# sch.net
KiCad netlist of a schematic drawn in Altium Designer
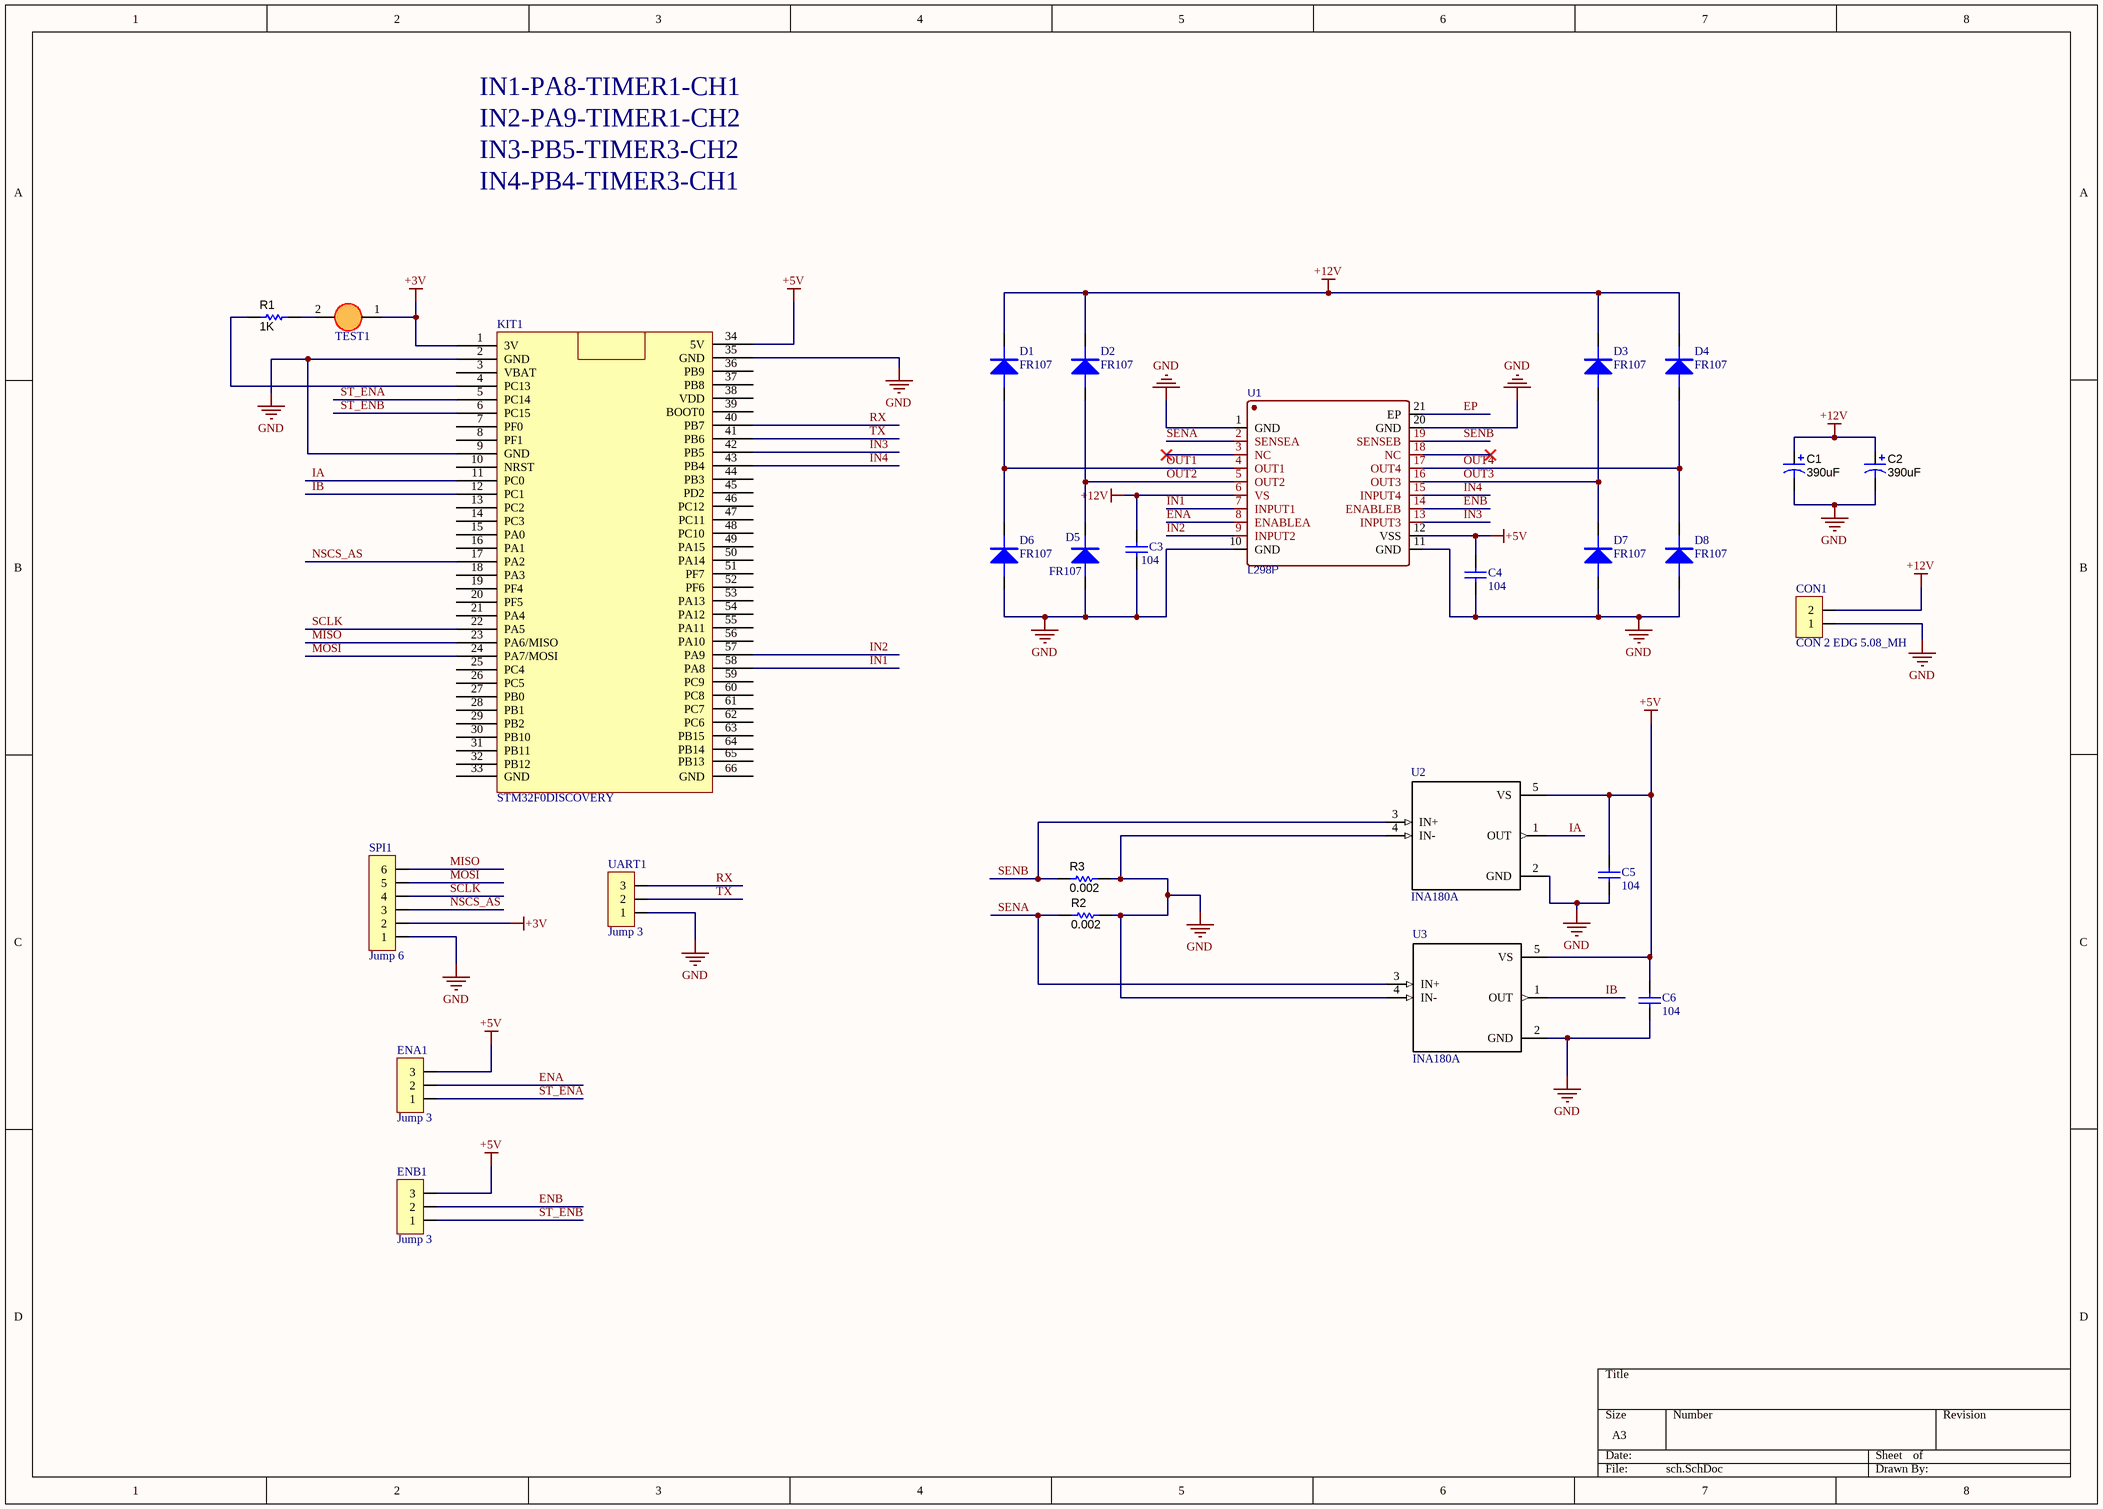
[diagram p0: sch.SchDoc]

(export (version "E")
  (design (tool "Eeschema 10.0.6"))
  (components
    (comp (ref "C1")
      (value "390uF")
      (footprint "CAP_12.5 X 25")
      (description "CAP ALUM 390UF 20% 50V RADIAL")
      (fields
        (field (name "PARTNUMBER") "UHW1H391MPD6")
        (field (name "MANUFACTURER") "Nichicon")
        (field (name "VALUEDISPLAYED") "390uF")
        (field (name "PUBLISHER") "Texas Instruments")
      )
      (libsource (lib "mySch") (part "Capacitor TuHoa"))
    )
    (comp (ref "C2")
      (value "390uF")
      (footprint "CAP_12.5 X 25")
      (description "CAP ALUM 390UF 20% 50V RADIAL")
      (fields
        (field (name "PARTNUMBER") "UHW1H391MPD6")
        (field (name "MANUFACTURER") "Nichicon")
        (field (name "VALUEDISPLAYED") "390uF")
        (field (name "PUBLISHER") "Texas Instruments")
      )
      (libsource (lib "mySch") (part "Capacitor TuHoa"))
    )
    (comp (ref "C3")
      (value "104")
      (footprint "TU_SMD_0805")
      (description "Ceramic Chip Capacitor - Standard")
      (fields (field (name "PUBLISHER") "Altium Limited"))
      (libsource (lib "mySch") (part "Capacitor 0805"))
    )
    (comp (ref "C4")
      (value "104")
      (footprint "TU_SMD_0805")
      (description "Ceramic Chip Capacitor - Standard")
      (fields (field (name "PUBLISHER") "Altium Limited"))
      (libsource (lib "mySch") (part "Capacitor 0805"))
    )
    (comp (ref "C5")
      (value "104")
      (footprint "TU_SMD_0805")
      (description "Ceramic Chip Capacitor - Standard")
      (fields (field (name "PUBLISHER") "Altium Limited"))
      (libsource (lib "mySch") (part "Capacitor 0805"))
    )
    (comp (ref "C6")
      (value "104")
      (footprint "TU_SMD_0805")
      (description "Ceramic Chip Capacitor - Standard")
      (fields (field (name "PUBLISHER") "Altium Limited"))
      (libsource (lib "mySch") (part "Capacitor 0805"))
    )
    (comp (ref "CON1")
      (value "CON 2 EDG 5.08_MH")
      (footprint "CON 2 EDG 5.08")
      (description "CON 2 EDG 5.08 (xanh cong)")
      (libsource (lib "mySch") (part "CON 2 EDG 5.08_MH"))
    )
    (comp (ref "D1")
      (value "FR107")
      (footprint "D2A")
      (description "Diode 1N4148 DO35 450mA 100V ( 1N4148 DIP)")
      (libsource (lib "mySch") (part "Diode 1N4148 DO35 450mA 100V ( 1N4148 DIP)_MH"))
    )
    (comp (ref "D2")
      (value "FR107")
      (footprint "D2A")
      (description "Diode 1N4148 DO35 450mA 100V ( 1N4148 DIP)")
      (libsource (lib "mySch") (part "Diode 1N4148 DO35 450mA 100V ( 1N4148 DIP)_MH"))
    )
    (comp (ref "D3")
      (value "FR107")
      (footprint "D2A")
      (description "Diode 1N4148 DO35 450mA 100V ( 1N4148 DIP)")
      (libsource (lib "mySch") (part "Diode 1N4148 DO35 450mA 100V ( 1N4148 DIP)_MH"))
    )
    (comp (ref "D4")
      (value "FR107")
      (footprint "D2A")
      (description "Diode 1N4148 DO35 450mA 100V ( 1N4148 DIP)")
      (libsource (lib "mySch") (part "Diode 1N4148 DO35 450mA 100V ( 1N4148 DIP)_MH"))
    )
    (comp (ref "D5")
      (value "FR107")
      (footprint "D2A")
      (description "Diode 1N4148 DO35 450mA 100V ( 1N4148 DIP)")
      (libsource (lib "mySch") (part "Diode 1N4148 DO35 450mA 100V ( 1N4148 DIP)_MH"))
    )
    (comp (ref "D6")
      (value "FR107")
      (footprint "D2A")
      (description "Diode 1N4148 DO35 450mA 100V ( 1N4148 DIP)")
      (libsource (lib "mySch") (part "Diode 1N4148 DO35 450mA 100V ( 1N4148 DIP)_MH"))
    )
    (comp (ref "D7")
      (value "FR107")
      (footprint "D2A")
      (description "Diode 1N4148 DO35 450mA 100V ( 1N4148 DIP)")
      (libsource (lib "mySch") (part "Diode 1N4148 DO35 450mA 100V ( 1N4148 DIP)_MH"))
    )
    (comp (ref "D8")
      (value "FR107")
      (footprint "D2A")
      (description "Diode 1N4148 DO35 450mA 100V ( 1N4148 DIP)")
      (libsource (lib "mySch") (part "Diode 1N4148 DO35 450mA 100V ( 1N4148 DIP)_MH"))
    )
    (comp (ref "ENA1")
      (value "Jump 3")
      (footprint "Jump 3")
      (description "Jump 3P 2.54")
      (libsource (lib "mySch") (part "Jump 3"))
    )
    (comp (ref "ENB1")
      (value "Jump 3")
      (footprint "Jump 3")
      (description "Jump 3P 2.54")
      (libsource (lib "mySch") (part "Jump 3"))
    )
    (comp (ref "KIT1")
      (value "STM32F0DISCOVERY")
      (footprint "STM32F0DISCOVERY")
      (libsource (lib "mySch") (part "STM32F0DISCOVERY"))
    )
    (comp (ref "R1")
      (value "1K")
      (footprint "Tro SMD 0805")
      (description "RES, 100, 1%, 0.1 W, 0402")
      (fields
        (field (name "PARTNUMBER") "ERJ-2RKF1000X")
        (field (name "MANUFACTURER") "Panasonic")
        (field (name "PUBLISHER") "Texas Instruments")
      )
      (libsource (lib "mySch") (part "R nho"))
    )
    (comp (ref "R2")
      (value "0.002")
      (footprint "2512_R")
      (description "RES, 100, 1%, 0.1 W, 0402")
      (fields
        (field (name "PARTNUMBER") "ERJ-2RKF1000X")
        (field (name "MANUFACTURER") "Panasonic")
        (field (name "PUBLISHER") "Texas Instruments")
      )
      (libsource (lib "mySch") (part "R nho"))
    )
    (comp (ref "R3")
      (value "0.002")
      (footprint "2512_R")
      (description "RES, 100, 1%, 0.1 W, 0402")
      (fields
        (field (name "PARTNUMBER") "ERJ-2RKF1000X")
        (field (name "MANUFACTURER") "Panasonic")
        (field (name "PUBLISHER") "Texas Instruments")
      )
      (libsource (lib "mySch") (part "R nho"))
    )
    (comp (ref "SPI1")
      (value "Jump 6")
      (footprint "Jump 6")
      (description "Jump 6P 2.54")
      (libsource (lib "mySch") (part "Jump 6"))
    )
    (comp (ref "TEST1")
      (value "LED")
      (footprint "LED_0805")
      (description "LED 3mm")
      (libsource (lib "mySch") (part "LED SMD_0805_MH"))
    )
    (comp (ref "U1")
      (value "L298P")
      (footprint "SOIC127P1420X360-21N")
      (fields (field (name "BOM_SUPPLIER PART") "C85595"))
      (libsource (lib "mySch") (part "L298P"))
    )
    (comp (ref "U2")
      (value "INA180A")
      (footprint "SOT95P280X145-5N")
      (libsource (lib "mySch") (part "INA180A"))
    )
    (comp (ref "U3")
      (value "INA180A")
      (footprint "SOT95P280X145-5N")
      (libsource (lib "mySch") (part "INA180A"))
    )
    (comp (ref "UART1")
      (value "Jump 3")
      (footprint "Jump 3")
      (description "Jump 3P 2.54")
      (libsource (lib "mySch") (part "Jump 3"))
    )
  )
  (nets
    (net (code "1") (name "+3V") (class "Default")
      (node (ref "KIT1") (pin "1") (pinfunction "3V_1") (pintype "passive"))
      (node (ref "SPI1") (pin "2") (pinfunction "2_2") (pintype "passive"))
      (node (ref "TEST1") (pin "1") (pinfunction "A_1") (pintype "passive"))
    )
    (net (code "2") (name "+5V") (class "Default")
      (node (ref "C4") (pin "2") (pinfunction "2_2") (pintype "passive"))
      (node (ref "C5") (pin "2") (pinfunction "2_2") (pintype "passive"))
      (node (ref "C6") (pin "2") (pinfunction "2_2") (pintype "passive"))
      (node (ref "ENA1") (pin "3") (pinfunction "3_3") (pintype "passive"))
      (node (ref "ENB1") (pin "3") (pinfunction "3_3") (pintype "passive"))
      (node (ref "KIT1") (pin "34") (pinfunction "5V_34") (pintype "passive"))
      (node (ref "U1") (pin "12") (pinfunction "VSS_12") (pintype "passive"))
      (node (ref "U2") (pin "5") (pinfunction "VS_5") (pintype "power_in"))
      (node (ref "U3") (pin "5") (pinfunction "VS_5") (pintype "power_in"))
    )
    (net (code "3") (name "+12V") (class "Default")
      (node (ref "C1") (pin "1") (pinfunction "+_1") (pintype "passive"))
      (node (ref "C2") (pin "1") (pinfunction "+_1") (pintype "passive"))
      (node (ref "C3") (pin "2") (pinfunction "2_2") (pintype "passive"))
      (node (ref "CON1") (pin "2") (pinfunction "2_2") (pintype "passive"))
      (node (ref "D1") (pin "2") (pinfunction "2_2") (pintype "passive"))
      (node (ref "D2") (pin "2") (pinfunction "2_2") (pintype "passive"))
      (node (ref "D3") (pin "2") (pinfunction "2_2") (pintype "passive"))
      (node (ref "D4") (pin "2") (pinfunction "2_2") (pintype "passive"))
      (node (ref "U1") (pin "6") (pinfunction "VS_6") (pintype "passive"))
    )
    (net (code "4") (name "/ENA") (class "Default")
      (node (ref "ENA1") (pin "2") (pinfunction "2_2") (pintype "passive"))
      (node (ref "U1") (pin "8") (pinfunction "ENABLEA_8") (pintype "passive"))
    )
    (net (code "5") (name "/ENB") (class "Default")
      (node (ref "ENB1") (pin "2") (pinfunction "2_2") (pintype "passive"))
      (node (ref "U1") (pin "14") (pinfunction "ENABLEB_14") (pintype "passive"))
    )
    (net (code "6") (name "/EP") (class "Default")
      (node (ref "U1") (pin "21") (pinfunction "EP_21") (pintype "passive"))
    )
    (net (code "7") (name "/IA") (class "Default")
      (node (ref "KIT1") (pin "11") (pinfunction "PC0_11") (pintype "passive"))
      (node (ref "U2") (pin "1") (pinfunction "OUT_1") (pintype "output"))
    )
    (net (code "8") (name "/IB") (class "Default")
      (node (ref "KIT1") (pin "12") (pinfunction "PC1_12") (pintype "passive"))
      (node (ref "U3") (pin "1") (pinfunction "OUT_1") (pintype "output"))
    )
    (net (code "9") (name "/IN1") (class "Default")
      (node (ref "KIT1") (pin "58") (pinfunction "PA8_58") (pintype "passive"))
      (node (ref "U1") (pin "7") (pinfunction "INPUT1_7") (pintype "passive"))
    )
    (net (code "10") (name "/IN2") (class "Default")
      (node (ref "KIT1") (pin "57") (pinfunction "PA9_57") (pintype "passive"))
      (node (ref "U1") (pin "9") (pinfunction "INPUT2_9") (pintype "passive"))
    )
    (net (code "11") (name "/IN3") (class "Default")
      (node (ref "KIT1") (pin "42") (pinfunction "PB5_42") (pintype "passive"))
      (node (ref "U1") (pin "13") (pinfunction "INPUT3_13") (pintype "passive"))
    )
    (net (code "12") (name "/IN4") (class "Default")
      (node (ref "KIT1") (pin "43") (pinfunction "PB4_43") (pintype "passive"))
      (node (ref "U1") (pin "15") (pinfunction "INPUT4_15") (pintype "passive"))
    )
    (net (code "13") (name "/MISO") (class "Default")
      (node (ref "KIT1") (pin "23") (pinfunction "PA6/MISO_23") (pintype "passive"))
      (node (ref "SPI1") (pin "6") (pinfunction "6_6") (pintype "passive"))
    )
    (net (code "14") (name "/MOSI") (class "Default")
      (node (ref "KIT1") (pin "24") (pinfunction "PA7/MOSI_24") (pintype "passive"))
      (node (ref "SPI1") (pin "5") (pinfunction "5_5") (pintype "passive"))
    )
    (net (code "15") (name "/NSCS_AS") (class "Default")
      (node (ref "KIT1") (pin "17") (pinfunction "PA2_17") (pintype "passive"))
      (node (ref "SPI1") (pin "3") (pinfunction "3_3") (pintype "passive"))
    )
    (net (code "16") (name "/OUT1") (class "Default")
      (node (ref "D1") (pin "1") (pinfunction "1_1") (pintype "passive"))
      (node (ref "D6") (pin "2") (pinfunction "2_2") (pintype "passive"))
      (node (ref "U1") (pin "4") (pinfunction "OUT1_4") (pintype "passive"))
    )
    (net (code "17") (name "/OUT2") (class "Default")
      (node (ref "D2") (pin "1") (pinfunction "1_1") (pintype "passive"))
      (node (ref "D5") (pin "2") (pinfunction "2_2") (pintype "passive"))
      (node (ref "U1") (pin "5") (pinfunction "OUT2_5") (pintype "passive"))
    )
    (net (code "18") (name "/OUT3") (class "Default")
      (node (ref "D3") (pin "1") (pinfunction "1_1") (pintype "passive"))
      (node (ref "D7") (pin "2") (pinfunction "2_2") (pintype "passive"))
      (node (ref "U1") (pin "16") (pinfunction "OUT3_16") (pintype "passive"))
    )
    (net (code "19") (name "/OUT4") (class "Default")
      (node (ref "D4") (pin "1") (pinfunction "1_1") (pintype "passive"))
      (node (ref "D8") (pin "2") (pinfunction "2_2") (pintype "passive"))
      (node (ref "U1") (pin "17") (pinfunction "OUT4_17") (pintype "passive"))
    )
    (net (code "20") (name "/RX") (class "Default")
      (node (ref "KIT1") (pin "40") (pinfunction "PB7_40") (pintype "passive"))
      (node (ref "UART1") (pin "3") (pinfunction "3_3") (pintype "passive"))
    )
    (net (code "21") (name "/SCLK") (class "Default")
      (node (ref "KIT1") (pin "22") (pinfunction "PA5_22") (pintype "passive"))
      (node (ref "SPI1") (pin "4") (pinfunction "4_4") (pintype "passive"))
    )
    (net (code "22") (name "/SENA") (class "Default")
      (node (ref "R2") (pin "2") (pinfunction "2_2") (pintype "passive"))
      (node (ref "U1") (pin "2") (pinfunction "SENSEA_2") (pintype "passive"))
      (node (ref "U3") (pin "3") (pinfunction "IN+_3") (pintype "input"))
    )
    (net (code "23") (name "/SENB") (class "Default")
      (node (ref "R3") (pin "2") (pinfunction "2_2") (pintype "passive"))
      (node (ref "U1") (pin "19") (pinfunction "SENSEB_19") (pintype "passive"))
      (node (ref "U2") (pin "3") (pinfunction "IN+_3") (pintype "input"))
    )
    (net (code "24") (name "/ST_ENA") (class "Default")
      (node (ref "ENA1") (pin "1") (pinfunction "1_1") (pintype "passive"))
      (node (ref "KIT1") (pin "5") (pinfunction "PC14_5") (pintype "passive"))
    )
    (net (code "25") (name "/ST_ENB") (class "Default")
      (node (ref "ENB1") (pin "1") (pinfunction "1_1") (pintype "passive"))
      (node (ref "KIT1") (pin "6") (pinfunction "PC15_6") (pintype "passive"))
    )
    (net (code "26") (name "/TX") (class "Default")
      (node (ref "KIT1") (pin "41") (pinfunction "PB6_41") (pintype "passive"))
      (node (ref "UART1") (pin "2") (pinfunction "2_2") (pintype "passive"))
    )
    (net (code "27") (name "GND") (class "Default")
      (node (ref "C1") (pin "2") (pinfunction "-_2") (pintype "passive"))
      (node (ref "C2") (pin "2") (pinfunction "-_2") (pintype "passive"))
      (node (ref "C3") (pin "1") (pinfunction "1_1") (pintype "passive"))
      (node (ref "C4") (pin "1") (pinfunction "1_1") (pintype "passive"))
      (node (ref "C5") (pin "1") (pinfunction "1_1") (pintype "passive"))
      (node (ref "C6") (pin "1") (pinfunction "1_1") (pintype "passive"))
      (node (ref "CON1") (pin "1") (pinfunction "1_1") (pintype "passive"))
      (node (ref "D5") (pin "1") (pinfunction "1_1") (pintype "passive"))
      (node (ref "D6") (pin "1") (pinfunction "1_1") (pintype "passive"))
      (node (ref "D7") (pin "1") (pinfunction "1_1") (pintype "passive"))
      (node (ref "D8") (pin "1") (pinfunction "1_1") (pintype "passive"))
      (node (ref "KIT1") (pin "2") (pinfunction "GND_2") (pintype "passive"))
      (node (ref "KIT1") (pin "35") (pinfunction "GND_35") (pintype "passive"))
      (node (ref "KIT1") (pin "9") (pinfunction "GND_9") (pintype "passive"))
      (node (ref "R2") (pin "1") (pinfunction "1_1") (pintype "passive"))
      (node (ref "R3") (pin "1") (pinfunction "1_1") (pintype "passive"))
      (node (ref "SPI1") (pin "1") (pinfunction "1_1") (pintype "passive"))
      (node (ref "U1") (pin "1") (pinfunction "GND_1") (pintype "passive"))
      (node (ref "U1") (pin "10") (pinfunction "GND_10") (pintype "passive"))
      (node (ref "U1") (pin "11") (pinfunction "GND_11") (pintype "passive"))
      (node (ref "U1") (pin "20") (pinfunction "GND_20") (pintype "passive"))
      (node (ref "U2") (pin "2") (pinfunction "GND_2") (pintype "power_in"))
      (node (ref "U2") (pin "4") (pinfunction "IN-_4") (pintype "input"))
      (node (ref "U3") (pin "2") (pinfunction "GND_2") (pintype "power_in"))
      (node (ref "U3") (pin "4") (pinfunction "IN-_4") (pintype "input"))
      (node (ref "UART1") (pin "1") (pinfunction "1_1") (pintype "passive"))
    )
    (net (code "28") (name "Net-(KIT1-PC13)") (class "Default")
      (node (ref "KIT1") (pin "4") (pinfunction "PC13_4") (pintype "passive"))
      (node (ref "R1") (pin "1") (pinfunction "1_1") (pintype "passive"))
    )
    (net (code "29") (name "Net-(TEST1-K)") (class "Default")
      (node (ref "R1") (pin "2") (pinfunction "2_2") (pintype "passive"))
      (node (ref "TEST1") (pin "2") (pinfunction "K_2") (pintype "passive"))
    )
    (net (code "30") (name "unconnected-(KIT1-BOOT0-Pad39)") (class "Default")
      (node (ref "KIT1") (pin "39") (pinfunction "BOOT0_39") (pintype "passive"))
    )
    (net (code "31") (name "unconnected-(KIT1-GND-Pad33)") (class "Default")
      (node (ref "KIT1") (pin "33") (pinfunction "GND_33") (pintype "passive"))
    )
    (net (code "32") (name "unconnected-(KIT1-GND-Pad66)") (class "Default")
      (node (ref "KIT1") (pin "66") (pinfunction "GND_66") (pintype "passive"))
    )
    (net (code "33") (name "unconnected-(KIT1-NRST-Pad10)") (class "Default")
      (node (ref "KIT1") (pin "10") (pinfunction "NRST_10") (pintype "passive"))
    )
    (net (code "34") (name "unconnected-(KIT1-PA0-Pad15)") (class "Default")
      (node (ref "KIT1") (pin "15") (pinfunction "PA0_15") (pintype "passive"))
    )
    (net (code "35") (name "unconnected-(KIT1-PA1-Pad16)") (class "Default")
      (node (ref "KIT1") (pin "16") (pinfunction "PA1_16") (pintype "passive"))
    )
    (net (code "36") (name "unconnected-(KIT1-PA3-Pad18)") (class "Default")
      (node (ref "KIT1") (pin "18") (pinfunction "PA3_18") (pintype "passive"))
    )
    (net (code "37") (name "unconnected-(KIT1-PA4-Pad21)") (class "Default")
      (node (ref "KIT1") (pin "21") (pinfunction "PA4_21") (pintype "passive"))
    )
    (net (code "38") (name "unconnected-(KIT1-PA10-Pad56)") (class "Default")
      (node (ref "KIT1") (pin "56") (pinfunction "PA10_56") (pintype "passive"))
    )
    (net (code "39") (name "unconnected-(KIT1-PA11-Pad55)") (class "Default")
      (node (ref "KIT1") (pin "55") (pinfunction "PA11_55") (pintype "passive"))
    )
    (net (code "40") (name "unconnected-(KIT1-PA12-Pad54)") (class "Default")
      (node (ref "KIT1") (pin "54") (pinfunction "PA12_54") (pintype "passive"))
    )
    (net (code "41") (name "unconnected-(KIT1-PA13-Pad53)") (class "Default")
      (node (ref "KIT1") (pin "53") (pinfunction "PA13_53") (pintype "passive"))
    )
    (net (code "42") (name "unconnected-(KIT1-PA14-Pad50)") (class "Default")
      (node (ref "KIT1") (pin "50") (pinfunction "PA14_50") (pintype "passive"))
    )
    (net (code "43") (name "unconnected-(KIT1-PA15-Pad49)") (class "Default")
      (node (ref "KIT1") (pin "49") (pinfunction "PA15_49") (pintype "passive"))
    )
    (net (code "44") (name "unconnected-(KIT1-PB0-Pad27)") (class "Default")
      (node (ref "KIT1") (pin "27") (pinfunction "PB0_27") (pintype "passive"))
    )
    (net (code "45") (name "unconnected-(KIT1-PB1-Pad28)") (class "Default")
      (node (ref "KIT1") (pin "28") (pinfunction "PB1_28") (pintype "passive"))
    )
    (net (code "46") (name "unconnected-(KIT1-PB2-Pad29)") (class "Default")
      (node (ref "KIT1") (pin "29") (pinfunction "PB2_29") (pintype "passive"))
    )
    (net (code "47") (name "unconnected-(KIT1-PB3-Pad44)") (class "Default")
      (node (ref "KIT1") (pin "44") (pinfunction "PB3_44") (pintype "passive"))
    )
    (net (code "48") (name "unconnected-(KIT1-PB8-Pad37)") (class "Default")
      (node (ref "KIT1") (pin "37") (pinfunction "PB8_37") (pintype "passive"))
    )
    (net (code "49") (name "unconnected-(KIT1-PB9-Pad36)") (class "Default")
      (node (ref "KIT1") (pin "36") (pinfunction "PB9_36") (pintype "passive"))
    )
    (net (code "50") (name "unconnected-(KIT1-PB10-Pad30)") (class "Default")
      (node (ref "KIT1") (pin "30") (pinfunction "PB10_30") (pintype "passive"))
    )
    (net (code "51") (name "unconnected-(KIT1-PB11-Pad31)") (class "Default")
      (node (ref "KIT1") (pin "31") (pinfunction "PB11_31") (pintype "passive"))
    )
    (net (code "52") (name "unconnected-(KIT1-PB12-Pad32)") (class "Default")
      (node (ref "KIT1") (pin "32") (pinfunction "PB12_32") (pintype "passive"))
    )
    (net (code "53") (name "unconnected-(KIT1-PB13-Pad65)") (class "Default")
      (node (ref "KIT1") (pin "65") (pinfunction "PB13_65") (pintype "passive"))
    )
    (net (code "54") (name "unconnected-(KIT1-PB14-Pad64)") (class "Default")
      (node (ref "KIT1") (pin "64") (pinfunction "PB14_64") (pintype "passive"))
    )
    (net (code "55") (name "unconnected-(KIT1-PB15-Pad63)") (class "Default")
      (node (ref "KIT1") (pin "63") (pinfunction "PB15_63") (pintype "passive"))
    )
    (net (code "56") (name "unconnected-(KIT1-PC2-Pad13)") (class "Default")
      (node (ref "KIT1") (pin "13") (pinfunction "PC2_13") (pintype "passive"))
    )
    (net (code "57") (name "unconnected-(KIT1-PC3-Pad14)") (class "Default")
      (node (ref "KIT1") (pin "14") (pinfunction "PC3_14") (pintype "passive"))
    )
    (net (code "58") (name "unconnected-(KIT1-PC4-Pad25)") (class "Default")
      (node (ref "KIT1") (pin "25") (pinfunction "PC4_25") (pintype "passive"))
    )
    (net (code "59") (name "unconnected-(KIT1-PC5-Pad26)") (class "Default")
      (node (ref "KIT1") (pin "26") (pinfunction "PC5_26") (pintype "passive"))
    )
    (net (code "60") (name "unconnected-(KIT1-PC6-Pad62)") (class "Default")
      (node (ref "KIT1") (pin "62") (pinfunction "PC6_62") (pintype "passive"))
    )
    (net (code "61") (name "unconnected-(KIT1-PC7-Pad61)") (class "Default")
      (node (ref "KIT1") (pin "61") (pinfunction "PC7_61") (pintype "passive"))
    )
    (net (code "62") (name "unconnected-(KIT1-PC8-Pad60)") (class "Default")
      (node (ref "KIT1") (pin "60") (pinfunction "PC8_60") (pintype "passive"))
    )
    (net (code "63") (name "unconnected-(KIT1-PC9-Pad59)") (class "Default")
      (node (ref "KIT1") (pin "59") (pinfunction "PC9_59") (pintype "passive"))
    )
    (net (code "64") (name "unconnected-(KIT1-PC10-Pad48)") (class "Default")
      (node (ref "KIT1") (pin "48") (pinfunction "PC10_48") (pintype "passive"))
    )
    (net (code "65") (name "unconnected-(KIT1-PC11-Pad47)") (class "Default")
      (node (ref "KIT1") (pin "47") (pinfunction "PC11_47") (pintype "passive"))
    )
    (net (code "66") (name "unconnected-(KIT1-PC12-Pad46)") (class "Default")
      (node (ref "KIT1") (pin "46") (pinfunction "PC12_46") (pintype "passive"))
    )
    (net (code "67") (name "unconnected-(KIT1-PD2-Pad45)") (class "Default")
      (node (ref "KIT1") (pin "45") (pinfunction "PD2_45") (pintype "passive"))
    )
    (net (code "68") (name "unconnected-(KIT1-PF0-Pad7)") (class "Default")
      (node (ref "KIT1") (pin "7") (pinfunction "PF0_7") (pintype "passive"))
    )
    (net (code "69") (name "unconnected-(KIT1-PF1-Pad8)") (class "Default")
      (node (ref "KIT1") (pin "8") (pinfunction "PF1_8") (pintype "passive"))
    )
    (net (code "70") (name "unconnected-(KIT1-PF4-Pad19)") (class "Default")
      (node (ref "KIT1") (pin "19") (pinfunction "PF4_19") (pintype "passive"))
    )
    (net (code "71") (name "unconnected-(KIT1-PF5-Pad20)") (class "Default")
      (node (ref "KIT1") (pin "20") (pinfunction "PF5_20") (pintype "passive"))
    )
    (net (code "72") (name "unconnected-(KIT1-PF6-Pad52)") (class "Default")
      (node (ref "KIT1") (pin "52") (pinfunction "PF6_52") (pintype "passive"))
    )
    (net (code "73") (name "unconnected-(KIT1-PF7-Pad51)") (class "Default")
      (node (ref "KIT1") (pin "51") (pinfunction "PF7_51") (pintype "passive"))
    )
    (net (code "74") (name "unconnected-(KIT1-VBAT-Pad3)") (class "Default")
      (node (ref "KIT1") (pin "3") (pinfunction "VBAT_3") (pintype "passive"))
    )
    (net (code "75") (name "unconnected-(KIT1-VDD-Pad38)") (class "Default")
      (node (ref "KIT1") (pin "38") (pinfunction "VDD_38") (pintype "passive"))
    )
    (net (code "76") (name "unconnected-(U1-NC-Pad3)") (class "Default")
      (node (ref "U1") (pin "3") (pinfunction "NC_3") (pintype "passive+no_connect"))
    )
    (net (code "77") (name "unconnected-(U1-NC-Pad18)") (class "Default")
      (node (ref "U1") (pin "18") (pinfunction "NC_18") (pintype "passive+no_connect"))
    )
  )
)
